# Temp_controlled_fan.net
KiCad netlist of a schematic drawn in EAGLE
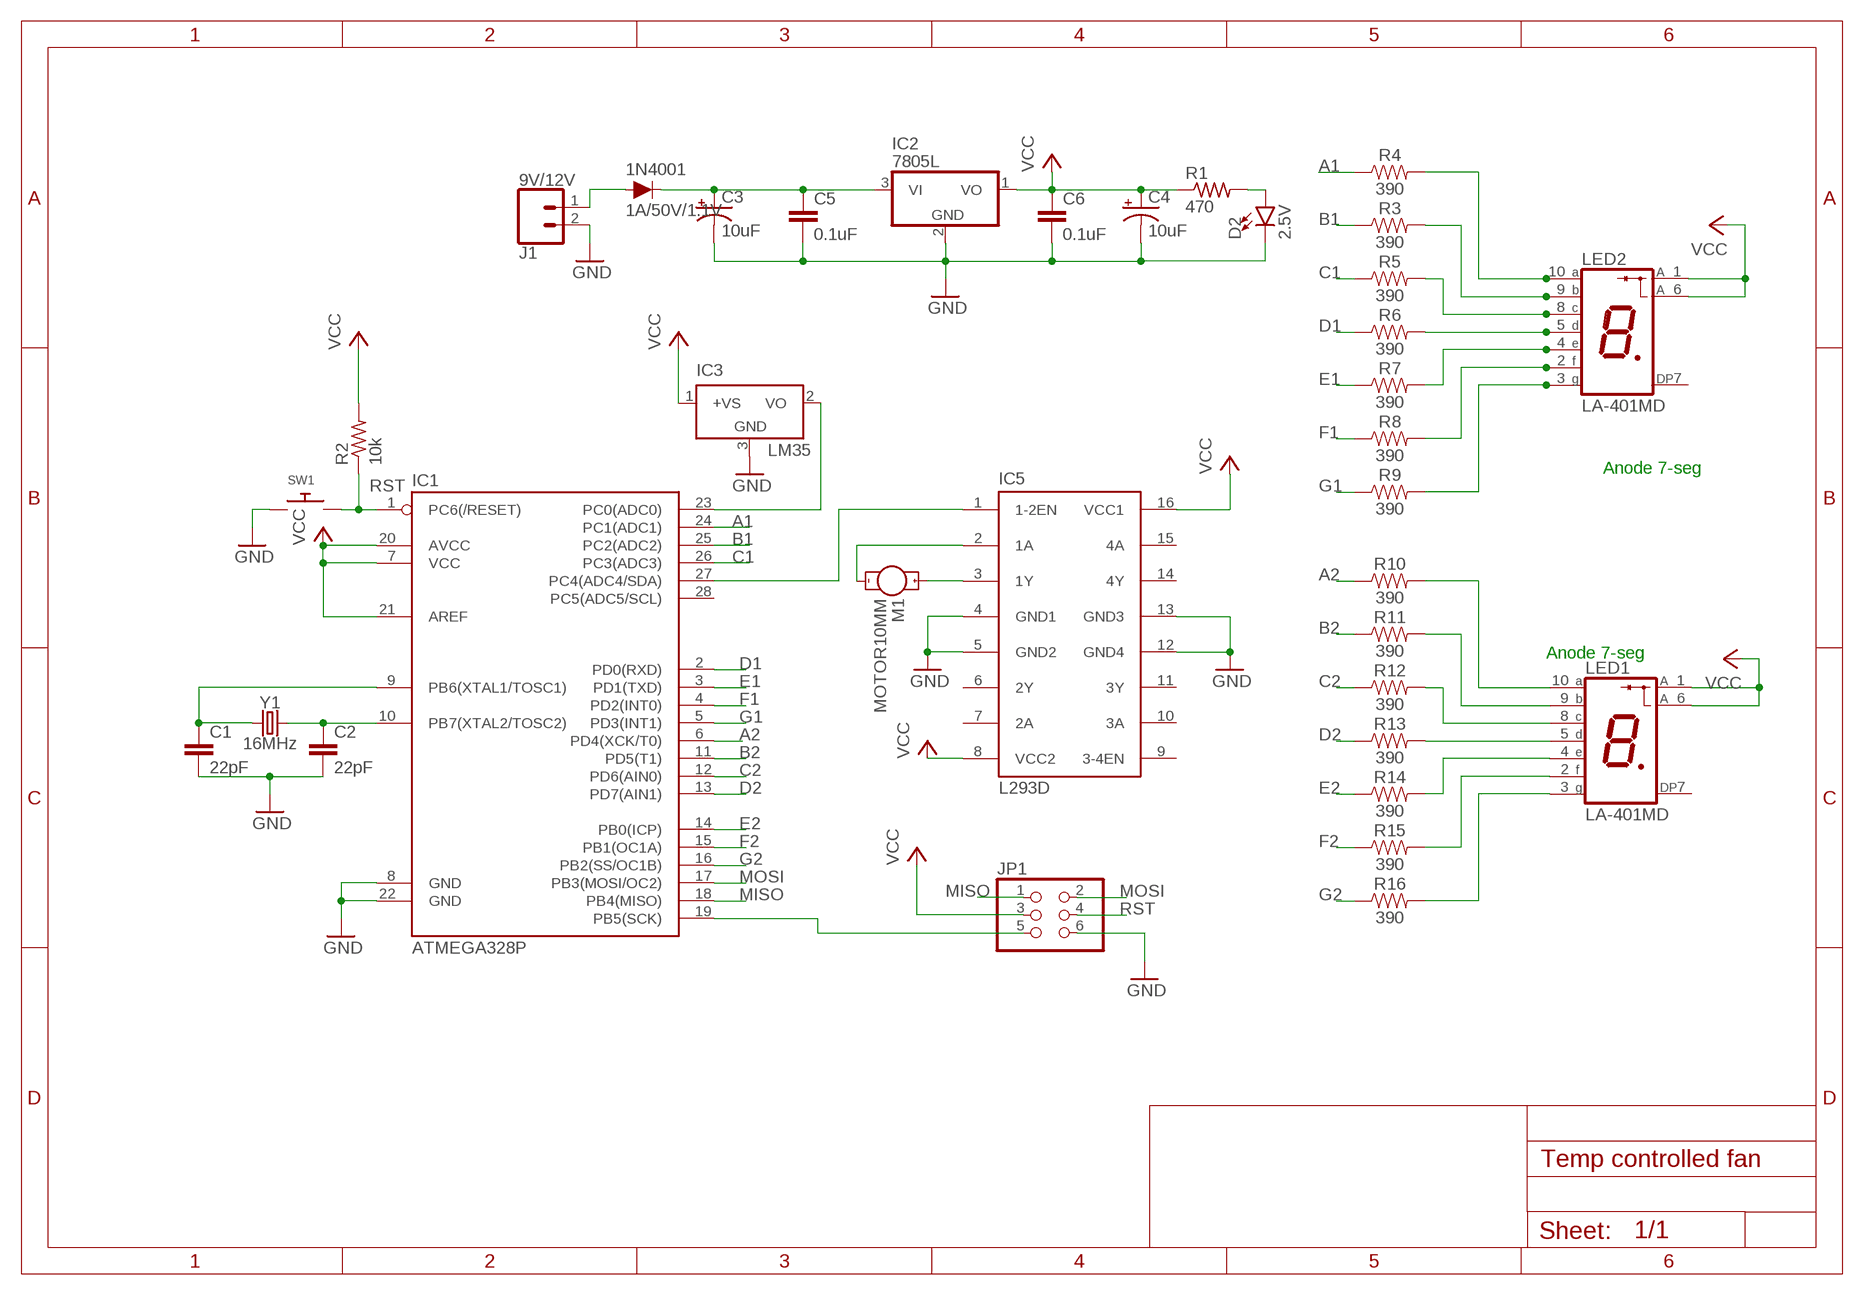
[diagram p0: schematic, sheet 1]

(export (version "E")
  (design (tool "Eeschema 10.0.6"))
  (components
    (comp (ref "1N4001")
      (value "1A/50V/1.1V")
      (footprint "eagle-import:DIODE-1N4001")
      (libsource (lib "eagle-import") (part "DIODE-PTH"))
    )
    (comp (ref "C1")
      (value "22pF")
      (footprint "eagle-import:0603")
      (libsource (lib "eagle-import") (part "22PF-0603-50V-5%"))
    )
    (comp (ref "C2")
      (value "22pF")
      (footprint "eagle-import:0603")
      (libsource (lib "eagle-import") (part "22PF-0603-50V-5%"))
    )
    (comp (ref "C3")
      (value "10uF")
      (footprint "eagle-import:CPOL-RADIAL-2.5MM-5MM")
      (libsource (lib "eagle-import") (part "10UF-POLAR-RADIAL-2.5MM-25V-20%"))
    )
    (comp (ref "C4")
      (value "10uF")
      (footprint "eagle-import:CPOL-RADIAL-2.5MM-5MM")
      (libsource (lib "eagle-import") (part "10UF-POLAR-RADIAL-2.5MM-25V-20%"))
    )
    (comp (ref "C5")
      (value "0.1uF")
      (footprint "eagle-import:0603")
      (libsource (lib "eagle-import") (part "0.1UF-0603-25V-5%"))
    )
    (comp (ref "C6")
      (value "0.1uF")
      (footprint "eagle-import:0603")
      (libsource (lib "eagle-import") (part "0.1UF-0603-25V-5%"))
    )
    (comp (ref "D2")
      (value "2.5V")
      (footprint "eagle-import:LED-1206")
      (libsource (lib "eagle-import") (part "LED1206"))
    )
    (comp (ref "IC1")
      (value "ATMEGA328P")
      (footprint "eagle-import:DIP28")
      (libsource (lib "eagle-import") (part "ATMEGA328P_PDIP"))
    )
    (comp (ref "IC2")
      (value "7805L")
      (footprint "eagle-import:TO92")
      (libsource (lib "eagle-import") (part "78L05"))
    )
    (comp (ref "IC3")
      (value "LM35")
      (footprint "eagle-import:TO92")
      (libsource (lib "eagle-import") (part "LM35CZ"))
    )
    (comp (ref "IC5")
      (value "L293D")
      (footprint "eagle-import:DIL16")
      (libsource (lib "eagle-import") (part "L293D"))
    )
    (comp (ref "J1")
      (value "9V/12V")
      (footprint "eagle-import:1X02_RA_PTH_FEMALE")
      (libsource (lib "eagle-import") (part "CONN_02PTH_RA_FEMALE"))
    )
    (comp (ref "JP1")
      (value "PINHD-2X3")
      (footprint "eagle-import:2X03")
      (libsource (lib "eagle-import") (part "PINHD-2X3"))
    )
    (comp (ref "LED1")
      (value "LA-401MD")
      (footprint "eagle-import:LA-401")
      (libsource (lib "eagle-import") (part "LA-401DM"))
    )
    (comp (ref "LED2")
      (value "LA-401MD")
      (footprint "eagle-import:LA-401")
      (libsource (lib "eagle-import") (part "LA-401DM"))
    )
    (comp (ref "M1")
      (value "MOTOR10MM")
      (footprint "eagle-import:VIBE-MOTOR-10MM")
      (libsource (lib "eagle-import") (part "MOTOR10MM"))
    )
    (comp (ref "R1")
      (value "470")
      (footprint "eagle-import:R1206")
      (libsource (lib "eagle-import") (part "R-US_R1206"))
    )
    (comp (ref "R2")
      (value "10k")
      (footprint "eagle-import:R1206")
      (libsource (lib "eagle-import") (part "R-US_R1206"))
    )
    (comp (ref "R3")
      (value "390")
      (footprint "eagle-import:0805")
      (libsource (lib "eagle-import") (part "RESISTOR0805"))
    )
    (comp (ref "R4")
      (value "390")
      (footprint "eagle-import:0805")
      (libsource (lib "eagle-import") (part "RESISTOR0805"))
    )
    (comp (ref "R5")
      (value "390")
      (footprint "eagle-import:0805")
      (libsource (lib "eagle-import") (part "RESISTOR0805"))
    )
    (comp (ref "R6")
      (value "390")
      (footprint "eagle-import:0805")
      (libsource (lib "eagle-import") (part "RESISTOR0805"))
    )
    (comp (ref "R7")
      (value "390")
      (footprint "eagle-import:0805")
      (libsource (lib "eagle-import") (part "RESISTOR0805"))
    )
    (comp (ref "R8")
      (value "390")
      (footprint "eagle-import:0805")
      (libsource (lib "eagle-import") (part "RESISTOR0805"))
    )
    (comp (ref "R9")
      (value "390")
      (footprint "eagle-import:0805")
      (libsource (lib "eagle-import") (part "RESISTOR0805"))
    )
    (comp (ref "R10")
      (value "390")
      (footprint "eagle-import:0805")
      (libsource (lib "eagle-import") (part "RESISTOR0805"))
    )
    (comp (ref "R11")
      (value "390")
      (footprint "eagle-import:0805")
      (libsource (lib "eagle-import") (part "RESISTOR0805"))
    )
    (comp (ref "R12")
      (value "390")
      (footprint "eagle-import:0805")
      (libsource (lib "eagle-import") (part "RESISTOR0805"))
    )
    (comp (ref "R13")
      (value "390")
      (footprint "eagle-import:0805")
      (libsource (lib "eagle-import") (part "RESISTOR0805"))
    )
    (comp (ref "R14")
      (value "390")
      (footprint "eagle-import:0805")
      (libsource (lib "eagle-import") (part "RESISTOR0805"))
    )
    (comp (ref "R15")
      (value "390")
      (footprint "eagle-import:0805")
      (libsource (lib "eagle-import") (part "RESISTOR0805"))
    )
    (comp (ref "R16")
      (value "390")
      (footprint "eagle-import:0805")
      (libsource (lib "eagle-import") (part "RESISTOR0805"))
    )
    (comp (ref "SW1")
      (value "SWITCH_PUSHBUTTONSOFTTOUCHSMD_SJ")
      (footprint "eagle-import:PUSHBUTTON_SMD_SJ")
      (libsource (lib "eagle-import") (part "SWITCH_PUSHBUTTONSOFTTOUCHSMD_SJ"))
    )
    (comp (ref "Y1")
      (value "16MHz")
      (footprint "eagle-import:HC49US")
      (libsource (lib "eagle-import") (part "CRYSTAL-16MHZPTH-HC49US"))
    )
  )
  (nets
    (net (code "1") (name "/A1") (class "Default")
      (node (ref "IC1") (pin "24") (pinfunction "PC1(ADC1)_24") (pintype "bidirectional"))
      (node (ref "R4") (pin "1") (pinfunction "1_1") (pintype "passive"))
    )
    (net (code "2") (name "/A2") (class "Default")
      (node (ref "IC1") (pin "6") (pinfunction "PD4(XCK/T0)_6") (pintype "bidirectional"))
      (node (ref "R10") (pin "1") (pinfunction "1_1") (pintype "passive"))
    )
    (net (code "3") (name "/B1") (class "Default")
      (node (ref "IC1") (pin "25") (pinfunction "PC2(ADC2)_25") (pintype "bidirectional"))
      (node (ref "R3") (pin "1") (pinfunction "1_1") (pintype "passive"))
    )
    (net (code "4") (name "/B2") (class "Default")
      (node (ref "IC1") (pin "11") (pinfunction "PD5(T1)_11") (pintype "bidirectional"))
      (node (ref "R11") (pin "1") (pinfunction "1_1") (pintype "passive"))
    )
    (net (code "5") (name "/C1") (class "Default")
      (node (ref "IC1") (pin "26") (pinfunction "PC3(ADC3)_26") (pintype "bidirectional"))
      (node (ref "R5") (pin "1") (pinfunction "1_1") (pintype "passive"))
    )
    (net (code "6") (name "/C2") (class "Default")
      (node (ref "IC1") (pin "12") (pinfunction "PD6(AIN0)_12") (pintype "bidirectional"))
      (node (ref "R12") (pin "1") (pinfunction "1_1") (pintype "passive"))
    )
    (net (code "7") (name "/D1") (class "Default")
      (node (ref "IC1") (pin "2") (pinfunction "PD0(RXD)_2") (pintype "bidirectional"))
      (node (ref "R6") (pin "1") (pinfunction "1_1") (pintype "passive"))
    )
    (net (code "8") (name "/D2") (class "Default")
      (node (ref "IC1") (pin "13") (pinfunction "PD7(AIN1)_13") (pintype "bidirectional"))
      (node (ref "R13") (pin "1") (pinfunction "1_1") (pintype "passive"))
    )
    (net (code "9") (name "/E1") (class "Default")
      (node (ref "IC1") (pin "3") (pinfunction "PD1(TXD)_3") (pintype "bidirectional"))
      (node (ref "R7") (pin "1") (pinfunction "1_1") (pintype "passive"))
    )
    (net (code "10") (name "/E2") (class "Default")
      (node (ref "IC1") (pin "14") (pinfunction "PB0(ICP)_14") (pintype "bidirectional"))
      (node (ref "R14") (pin "1") (pinfunction "1_1") (pintype "passive"))
    )
    (net (code "11") (name "/F1") (class "Default")
      (node (ref "IC1") (pin "4") (pinfunction "PD2(INT0)_4") (pintype "bidirectional"))
      (node (ref "R8") (pin "1") (pinfunction "1_1") (pintype "passive"))
    )
    (net (code "12") (name "/F2") (class "Default")
      (node (ref "IC1") (pin "15") (pinfunction "PB1(OC1A)_15") (pintype "bidirectional"))
      (node (ref "R15") (pin "1") (pinfunction "1_1") (pintype "passive"))
    )
    (net (code "13") (name "/G1") (class "Default")
      (node (ref "IC1") (pin "5") (pinfunction "PD3(INT1)_5") (pintype "bidirectional"))
      (node (ref "R9") (pin "1") (pinfunction "1_1") (pintype "passive"))
    )
    (net (code "14") (name "/G2") (class "Default")
      (node (ref "IC1") (pin "16") (pinfunction "PB2(SS/OC1B)_16") (pintype "bidirectional"))
      (node (ref "R16") (pin "1") (pinfunction "1_1") (pintype "passive"))
    )
    (net (code "15") (name "/MISO") (class "Default")
      (node (ref "IC1") (pin "18") (pinfunction "PB4(MISO)_18") (pintype "bidirectional"))
      (node (ref "JP1") (pin "1") (pinfunction "1_1") (pintype "passive"))
    )
    (net (code "16") (name "/MOSI") (class "Default")
      (node (ref "IC1") (pin "17") (pinfunction "PB3(MOSI/OC2)_17") (pintype "bidirectional"))
      (node (ref "JP1") (pin "2") (pinfunction "2_2") (pintype "passive"))
    )
    (net (code "17") (name "/RST") (class "Default")
      (node (ref "IC1") (pin "1") (pinfunction "PC6(/RESET)_1") (pintype "bidirectional"))
      (node (ref "JP1") (pin "4") (pinfunction "4_4") (pintype "passive"))
      (node (ref "R2") (pin "1") (pinfunction "1_1") (pintype "passive"))
      (node (ref "SW1") (pin "P$2") (pinfunction "P$2_P$2") (pintype "passive"))
    )
    (net (code "18") (name "GND") (class "Default")
      (node (ref "C1") (pin "2") (pinfunction "2_2") (pintype "passive"))
      (node (ref "C2") (pin "2") (pinfunction "2_2") (pintype "passive"))
      (node (ref "C3") (pin "2") (pinfunction "-_2") (pintype "passive"))
      (node (ref "C4") (pin "2") (pinfunction "-_2") (pintype "passive"))
      (node (ref "C5") (pin "2") (pinfunction "2_2") (pintype "passive"))
      (node (ref "C6") (pin "2") (pinfunction "2_2") (pintype "passive"))
      (node (ref "D2") (pin "C") (pinfunction "C_C") (pintype "passive"))
      (node (ref "IC1") (pin "22") (pinfunction "GND_22") (pintype "bidirectional"))
      (node (ref "IC1") (pin "8") (pinfunction "GND_8") (pintype "bidirectional"))
      (node (ref "IC2") (pin "2") (pinfunction "GND_2") (pintype "passive"))
      (node (ref "IC3") (pin "3") (pinfunction "GND_3") (pintype "power_in"))
      (node (ref "IC5") (pin "12") (pinfunction "GND4_12") (pintype "power_in"))
      (node (ref "IC5") (pin "13") (pinfunction "GND3_13") (pintype "power_in"))
      (node (ref "IC5") (pin "4") (pinfunction "GND1_4") (pintype "power_in"))
      (node (ref "IC5") (pin "5") (pinfunction "GND2_5") (pintype "power_in"))
      (node (ref "J1") (pin "2") (pinfunction "2_2") (pintype "passive"))
      (node (ref "JP1") (pin "6") (pinfunction "6_6") (pintype "passive"))
      (node (ref "SW1") (pin "P$1") (pinfunction "P$1_P$1") (pintype "passive"))
    )
    (net (code "19") (name "Net-(1N4001-PadA)") (class "Default")
      (node (ref "1N4001") (pin "A") (pinfunction "A_A") (pintype "passive"))
      (node (ref "J1") (pin "1") (pinfunction "1_1") (pintype "passive"))
    )
    (net (code "20") (name "Net-(C3-+)") (class "Default")
      (node (ref "1N4001") (pin "C") (pinfunction "C_C") (pintype "passive"))
      (node (ref "C3") (pin "1") (pinfunction "+_1") (pintype "passive"))
      (node (ref "C5") (pin "1") (pinfunction "1_1") (pintype "passive"))
      (node (ref "IC2") (pin "3") (pinfunction "VI_3") (pintype "input"))
    )
    (net (code "21") (name "Net-(D2-PadA)") (class "Default")
      (node (ref "D2") (pin "A") (pinfunction "A_A") (pintype "passive"))
      (node (ref "R1") (pin "2") (pinfunction "2_2") (pintype "passive"))
    )
    (net (code "22") (name "Net-(IC1-PB5(SCK))") (class "Default")
      (node (ref "IC1") (pin "19") (pinfunction "PB5(SCK)_19") (pintype "bidirectional"))
      (node (ref "JP1") (pin "5") (pinfunction "5_5") (pintype "passive"))
    )
    (net (code "23") (name "Net-(IC1-PB6(XTAL1{slash}TOSC1))") (class "Default")
      (node (ref "C1") (pin "1") (pinfunction "1_1") (pintype "passive"))
      (node (ref "IC1") (pin "9") (pinfunction "PB6(XTAL1/TOSC1)_9") (pintype "bidirectional"))
      (node (ref "Y1") (pin "1") (pinfunction "1_1") (pintype "passive"))
    )
    (net (code "24") (name "Net-(IC1-PB7(XTAL2{slash}TOSC2))") (class "Default")
      (node (ref "C2") (pin "1") (pinfunction "1_1") (pintype "passive"))
      (node (ref "IC1") (pin "10") (pinfunction "PB7(XTAL2/TOSC2)_10") (pintype "bidirectional"))
      (node (ref "Y1") (pin "2") (pinfunction "2_2") (pintype "passive"))
    )
    (net (code "25") (name "Net-(IC1-PC0(ADC0))") (class "Default")
      (node (ref "IC1") (pin "23") (pinfunction "PC0(ADC0)_23") (pintype "bidirectional"))
      (node (ref "IC3") (pin "2") (pinfunction "VO_2") (pintype "input"))
    )
    (net (code "26") (name "Net-(IC1-PC4(ADC4{slash}SDA))") (class "Default")
      (node (ref "IC1") (pin "27") (pinfunction "PC4(ADC4/SDA)_27") (pintype "bidirectional"))
      (node (ref "IC5") (pin "1") (pinfunction "1-2EN_1") (pintype "input"))
    )
    (net (code "27") (name "Net-(IC5-1A)") (class "Default")
      (node (ref "IC5") (pin "2") (pinfunction "1A_2") (pintype "input"))
      (node (ref "M1") (pin "-") (pinfunction "-_-") (pintype "bidirectional"))
    )
    (net (code "28") (name "Net-(IC5-1Y)") (class "Default")
      (node (ref "IC5") (pin "3") (pinfunction "1Y_3") (pintype "output"))
      (node (ref "M1") (pin "+") (pinfunction "+_+") (pintype "bidirectional"))
    )
    (net (code "29") (name "Net-(LED1-A-Pad10)") (class "Default")
      (node (ref "LED1") (pin "10") (pinfunction "A_10") (pintype "passive"))
      (node (ref "R10") (pin "2") (pinfunction "2_2") (pintype "passive"))
    )
    (net (code "30") (name "Net-(LED1-B)") (class "Default")
      (node (ref "LED1") (pin "9") (pinfunction "B_9") (pintype "passive"))
      (node (ref "R11") (pin "2") (pinfunction "2_2") (pintype "passive"))
    )
    (net (code "31") (name "Net-(LED1-C)") (class "Default")
      (node (ref "LED1") (pin "8") (pinfunction "C_8") (pintype "passive"))
      (node (ref "R12") (pin "2") (pinfunction "2_2") (pintype "passive"))
    )
    (net (code "32") (name "Net-(LED1-D)") (class "Default")
      (node (ref "LED1") (pin "5") (pinfunction "D_5") (pintype "passive"))
      (node (ref "R13") (pin "2") (pinfunction "2_2") (pintype "passive"))
    )
    (net (code "33") (name "Net-(LED1-E)") (class "Default")
      (node (ref "LED1") (pin "4") (pinfunction "E_4") (pintype "passive"))
      (node (ref "R14") (pin "2") (pinfunction "2_2") (pintype "passive"))
    )
    (net (code "34") (name "Net-(LED1-F)") (class "Default")
      (node (ref "LED1") (pin "2") (pinfunction "F_2") (pintype "passive"))
      (node (ref "R15") (pin "2") (pinfunction "2_2") (pintype "passive"))
    )
    (net (code "35") (name "Net-(LED1-G)") (class "Default")
      (node (ref "LED1") (pin "3") (pinfunction "G_3") (pintype "passive"))
      (node (ref "R16") (pin "2") (pinfunction "2_2") (pintype "passive"))
    )
    (net (code "36") (name "Net-(LED2-A-Pad10)") (class "Default")
      (node (ref "LED2") (pin "10") (pinfunction "A_10") (pintype "passive"))
      (node (ref "R4") (pin "2") (pinfunction "2_2") (pintype "passive"))
    )
    (net (code "37") (name "Net-(LED2-B)") (class "Default")
      (node (ref "LED2") (pin "9") (pinfunction "B_9") (pintype "passive"))
      (node (ref "R3") (pin "2") (pinfunction "2_2") (pintype "passive"))
    )
    (net (code "38") (name "Net-(LED2-C)") (class "Default")
      (node (ref "LED2") (pin "8") (pinfunction "C_8") (pintype "passive"))
      (node (ref "R5") (pin "2") (pinfunction "2_2") (pintype "passive"))
    )
    (net (code "39") (name "Net-(LED2-D)") (class "Default")
      (node (ref "LED2") (pin "5") (pinfunction "D_5") (pintype "passive"))
      (node (ref "R6") (pin "2") (pinfunction "2_2") (pintype "passive"))
    )
    (net (code "40") (name "Net-(LED2-E)") (class "Default")
      (node (ref "LED2") (pin "4") (pinfunction "E_4") (pintype "passive"))
      (node (ref "R7") (pin "2") (pinfunction "2_2") (pintype "passive"))
    )
    (net (code "41") (name "Net-(LED2-F)") (class "Default")
      (node (ref "LED2") (pin "2") (pinfunction "F_2") (pintype "passive"))
      (node (ref "R8") (pin "2") (pinfunction "2_2") (pintype "passive"))
    )
    (net (code "42") (name "Net-(LED2-G)") (class "Default")
      (node (ref "LED2") (pin "3") (pinfunction "G_3") (pintype "passive"))
      (node (ref "R9") (pin "2") (pinfunction "2_2") (pintype "passive"))
    )
    (net (code "43") (name "VCC") (class "Default")
      (node (ref "C4") (pin "1") (pinfunction "+_1") (pintype "passive"))
      (node (ref "C6") (pin "1") (pinfunction "1_1") (pintype "passive"))
      (node (ref "IC1") (pin "20") (pinfunction "AVCC_20") (pintype "bidirectional"))
      (node (ref "IC1") (pin "21") (pinfunction "AREF_21") (pintype "bidirectional"))
      (node (ref "IC1") (pin "7") (pinfunction "VCC_7") (pintype "bidirectional"))
      (node (ref "IC2") (pin "1") (pinfunction "VO_1") (pintype "passive"))
      (node (ref "IC3") (pin "1") (pinfunction "+VS_1") (pintype "input"))
      (node (ref "IC5") (pin "16") (pinfunction "VCC1_16") (pintype "power_in"))
      (node (ref "IC5") (pin "8") (pinfunction "VCC2_8") (pintype "power_in"))
      (node (ref "JP1") (pin "3") (pinfunction "3_3") (pintype "passive"))
      (node (ref "LED1") (pin "1") (pinfunction "A_1") (pintype "passive"))
      (node (ref "LED1") (pin "6") (pinfunction "A_6") (pintype "passive"))
      (node (ref "LED2") (pin "1") (pinfunction "A_1") (pintype "passive"))
      (node (ref "LED2") (pin "6") (pinfunction "A_6") (pintype "passive"))
      (node (ref "R1") (pin "1") (pinfunction "1_1") (pintype "passive"))
      (node (ref "R2") (pin "2") (pinfunction "2_2") (pintype "passive"))
    )
    (net (code "44") (name "unconnected-(IC1-PC5(ADC5{slash}SCL)-Pad28)") (class "Default")
      (node (ref "IC1") (pin "28") (pinfunction "PC5(ADC5/SCL)_28") (pintype "bidirectional"))
    )
    (net (code "45") (name "unconnected-(IC5-2A-Pad7)") (class "Default")
      (node (ref "IC5") (pin "7") (pinfunction "2A_7") (pintype "input"))
    )
    (net (code "46") (name "unconnected-(IC5-2Y-Pad6)") (class "Default")
      (node (ref "IC5") (pin "6") (pinfunction "2Y_6") (pintype "output"))
    )
    (net (code "47") (name "unconnected-(IC5-3-4EN-Pad9)") (class "Default")
      (node (ref "IC5") (pin "9") (pinfunction "3-4EN_9") (pintype "input"))
    )
    (net (code "48") (name "unconnected-(IC5-3A-Pad10)") (class "Default")
      (node (ref "IC5") (pin "10") (pinfunction "3A_10") (pintype "input"))
    )
    (net (code "49") (name "unconnected-(IC5-3Y-Pad11)") (class "Default")
      (node (ref "IC5") (pin "11") (pinfunction "3Y_11") (pintype "output"))
    )
    (net (code "50") (name "unconnected-(IC5-4A-Pad15)") (class "Default")
      (node (ref "IC5") (pin "15") (pinfunction "4A_15") (pintype "input"))
    )
    (net (code "51") (name "unconnected-(IC5-4Y-Pad14)") (class "Default")
      (node (ref "IC5") (pin "14") (pinfunction "4Y_14") (pintype "output"))
    )
    (net (code "52") (name "unconnected-(LED1-DP-Pad7)") (class "Default")
      (node (ref "LED1") (pin "7") (pinfunction "DP_7") (pintype "passive"))
    )
    (net (code "53") (name "unconnected-(LED2-DP-Pad7)") (class "Default")
      (node (ref "LED2") (pin "7") (pinfunction "DP_7") (pintype "passive"))
    )
  )
)
